# Sonde.net
KiCad netlist of a schematic drawn in EAGLE
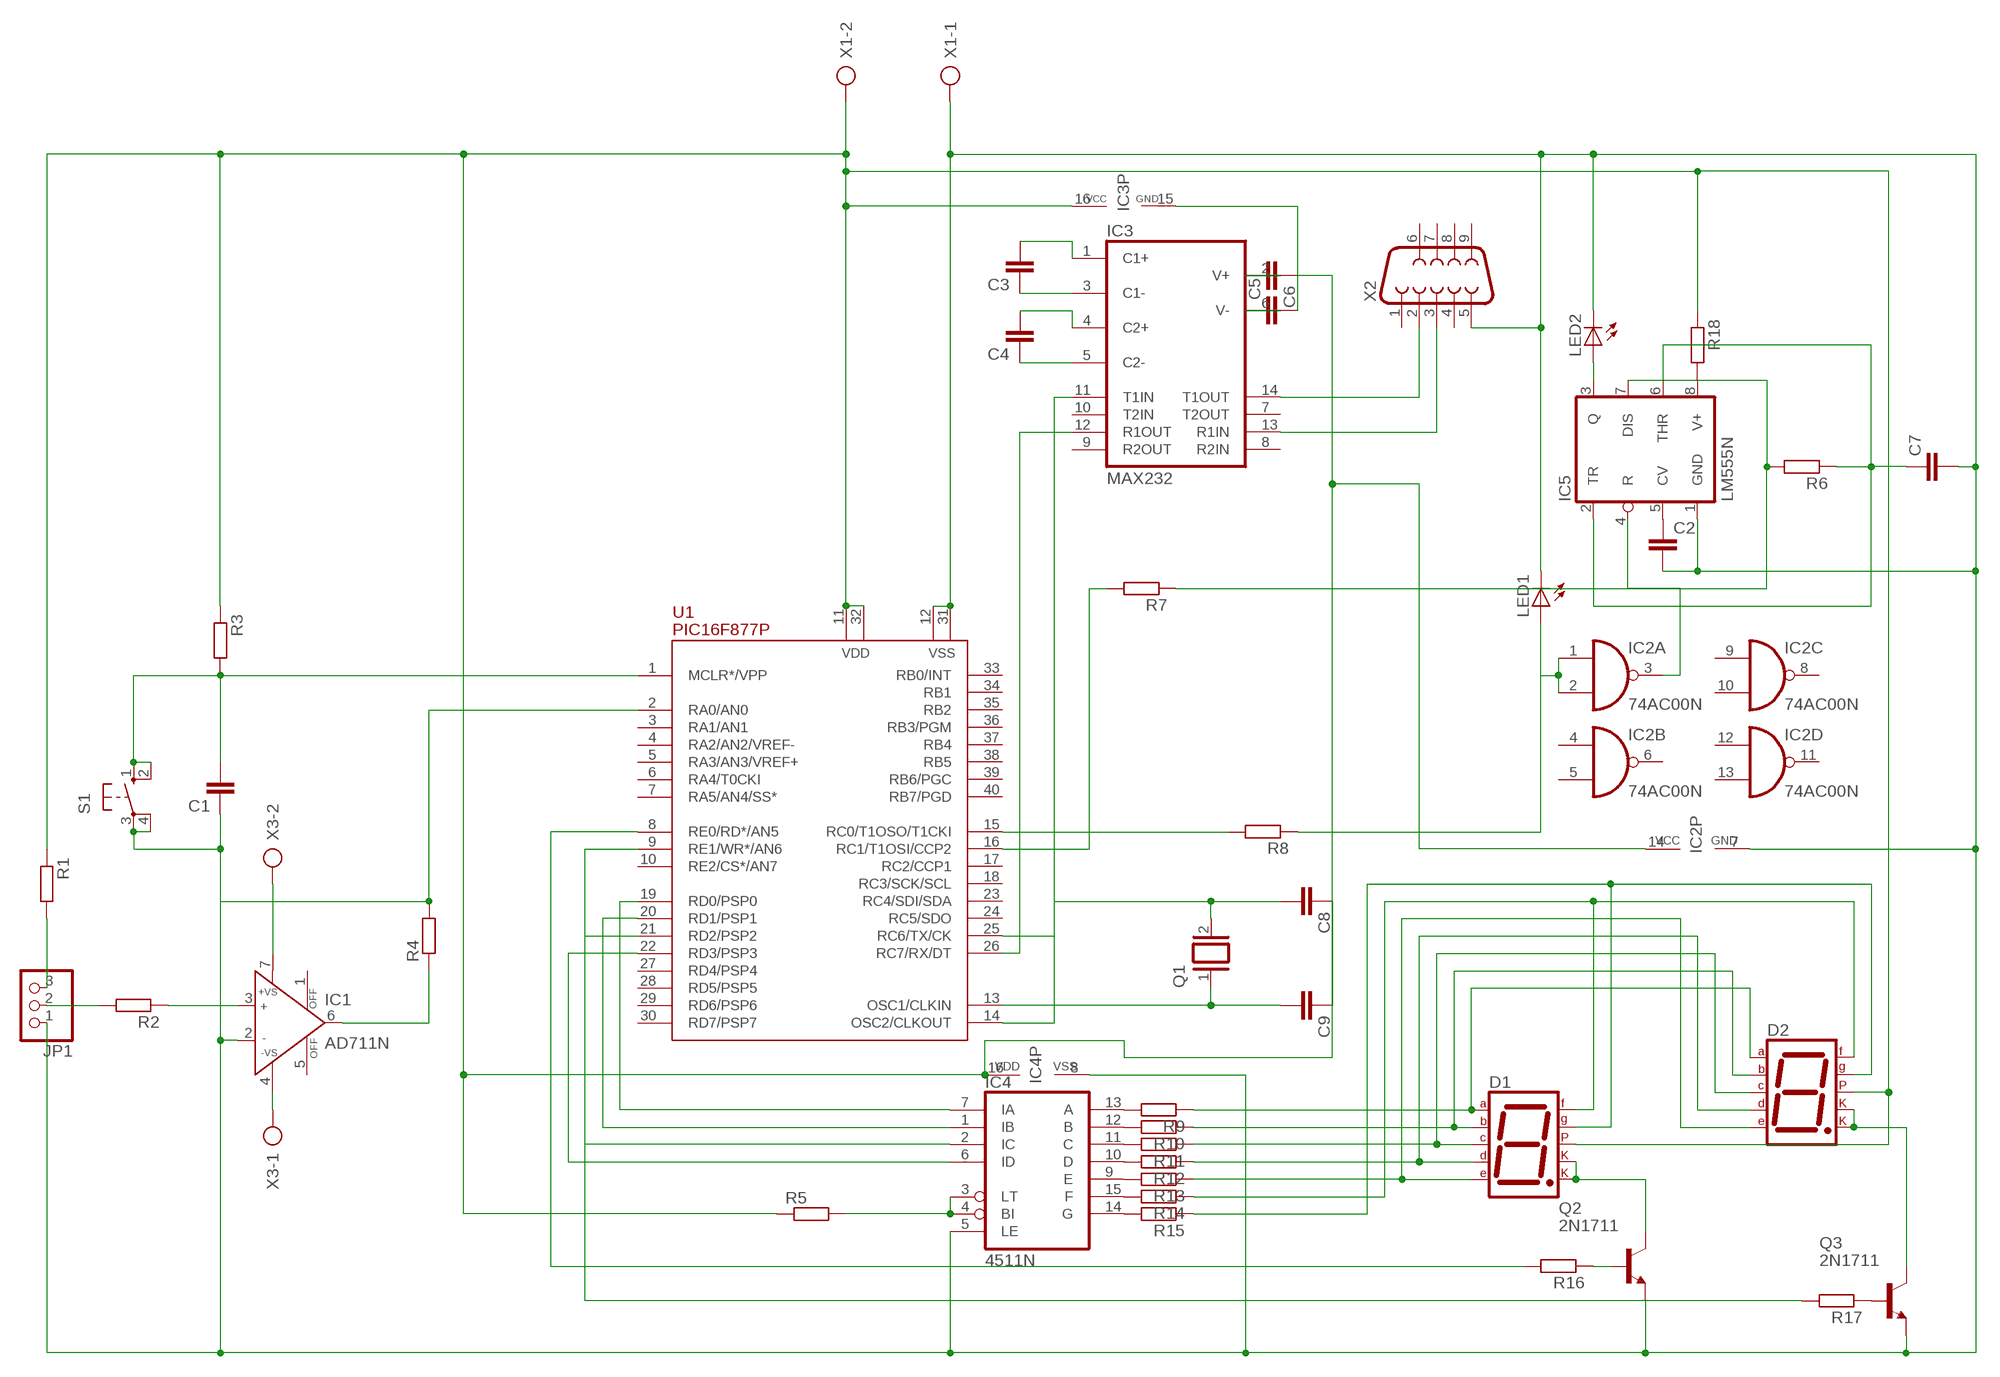
[diagram p0: schematic, sheet 1]

(export (version "E")
  (design (tool "Eeschema 10.0.6"))
  (components
    (comp (ref "C1")
      (value "C-EU025-024X044")
      (footprint "eagle-import:C025-024X044")
      (libsource (lib "eagle-import") (part "C-EU025-024X044"))
    )
    (comp (ref "C2")
      (value "C-EU025-024X044")
      (footprint "eagle-import:C025-024X044")
      (libsource (lib "eagle-import") (part "C-EU025-024X044"))
    )
    (comp (ref "C3")
      (value "C-EU025-024X044")
      (footprint "eagle-import:C025-024X044")
      (libsource (lib "eagle-import") (part "C-EU025-024X044"))
    )
    (comp (ref "C4")
      (value "C-EU025-024X044")
      (footprint "eagle-import:C025-024X044")
      (libsource (lib "eagle-import") (part "C-EU025-024X044"))
    )
    (comp (ref "C5")
      (value "C-EU025-024X044")
      (footprint "eagle-import:C025-024X044")
      (libsource (lib "eagle-import") (part "C-EU025-024X044"))
    )
    (comp (ref "C6")
      (value "C-EU025-024X044")
      (footprint "eagle-import:C025-024X044")
      (libsource (lib "eagle-import") (part "C-EU025-024X044"))
    )
    (comp (ref "C7")
      (value "C-EU025-024X044")
      (footprint "eagle-import:C025-024X044")
      (libsource (lib "eagle-import") (part "C-EU025-024X044"))
    )
    (comp (ref "C8")
      (value "C-EU025-024X044")
      (footprint "eagle-import:C025-024X044")
      (libsource (lib "eagle-import") (part "C-EU025-024X044"))
    )
    (comp (ref "C9")
      (value "C-EU025-024X044")
      (footprint "eagle-import:C025-024X044")
      (libsource (lib "eagle-import") (part "C-EU025-024X044"))
    )
    (comp (ref "D1")
      (value "7SEG-CK")
      (footprint "eagle-import:7SEG-13")
      (libsource (lib "eagle-import") (part "7SEG-CK"))
    )
    (comp (ref "D2")
      (value "7SEG-CK")
      (footprint "eagle-import:7SEG-13")
      (libsource (lib "eagle-import") (part "7SEG-CK"))
    )
    (comp (ref "IC1")
      (value "AD711N")
      (footprint "eagle-import:DIL08")
      (fields (field (name "MPN") "AD711BQ"))
      (libsource (lib "eagle-import") (part "AD711N"))
    )
    (comp (ref "IC2")
      (value "74AC00N")
      (footprint "eagle-import:DIL14")
      (libsource (lib "eagle-import") (part "7400NAC"))
    )
    (comp (ref "IC3")
      (value "MAX232")
      (footprint "eagle-import:DIL16")
      (fields (field (name "MF") "MAXIM") (field (name "MPN") "MAX232ACPE+"))
      (libsource (lib "eagle-import") (part "MAX232"))
    )
    (comp (ref "IC4")
      (value "4511N")
      (footprint "eagle-import:DIL16")
      (libsource (lib "eagle-import") (part "4511N"))
    )
    (comp (ref "IC5")
      (value "LM555N")
      (footprint "eagle-import:DIL08")
      (libsource (lib "eagle-import") (part "555NLM"))
    )
    (comp (ref "JP1")
      (value "PINHD-1X3")
      (footprint "eagle-import:1X03")
      (libsource (lib "eagle-import") (part "PINHD-1X3"))
    )
    (comp (ref "LED1")
      (value "LED_ELD260")
      (footprint "eagle-import:LED_LD260")
      (libsource (lib "eagle-import") (part "LED_ELD260"))
    )
    (comp (ref "LED2")
      (value "LED_ELD260")
      (footprint "eagle-import:LED_LD260")
      (libsource (lib "eagle-import") (part "LED_ELD260"))
    )
    (comp (ref "Q1")
      (value "XTAL/S")
      (footprint "eagle-import:QS")
      (libsource (lib "eagle-import") (part "XTAL/S"))
    )
    (comp (ref "Q2")
      (value "2N1711")
      (footprint "eagle-import:TO39")
      (libsource (lib "eagle-import") (part "2N1711"))
    )
    (comp (ref "Q3")
      (value "2N1711")
      (footprint "eagle-import:TO39")
      (libsource (lib "eagle-import") (part "2N1711"))
    )
    (comp (ref "R1")
      (value "R-EU_0207/10")
      (footprint "eagle-import:0207_10")
      (libsource (lib "eagle-import") (part "R-EU_0207/10"))
    )
    (comp (ref "R2")
      (value "R-EU_0207/10")
      (footprint "eagle-import:0207_10")
      (libsource (lib "eagle-import") (part "R-EU_0207/10"))
    )
    (comp (ref "R3")
      (value "R-EU_0207/10")
      (footprint "eagle-import:0207_10")
      (libsource (lib "eagle-import") (part "R-EU_0207/10"))
    )
    (comp (ref "R4")
      (value "R-EU_0207/10")
      (footprint "eagle-import:0207_10")
      (libsource (lib "eagle-import") (part "R-EU_0207/10"))
    )
    (comp (ref "R5")
      (value "R-EU_0207/10")
      (footprint "eagle-import:0207_10")
      (libsource (lib "eagle-import") (part "R-EU_0207/10"))
    )
    (comp (ref "R6")
      (value "R-EU_0207/10")
      (footprint "eagle-import:0207_10")
      (libsource (lib "eagle-import") (part "R-EU_0207/10"))
    )
    (comp (ref "R7")
      (value "R-EU_0207/10")
      (footprint "eagle-import:0207_10")
      (libsource (lib "eagle-import") (part "R-EU_0207/10"))
    )
    (comp (ref "R8")
      (value "R-EU_0207/10")
      (footprint "eagle-import:0207_10")
      (libsource (lib "eagle-import") (part "R-EU_0207/10"))
    )
    (comp (ref "R9")
      (value "R-EU_0207/10")
      (footprint "eagle-import:0207_10")
      (libsource (lib "eagle-import") (part "R-EU_0207/10"))
    )
    (comp (ref "R10")
      (value "R-EU_0207/10")
      (footprint "eagle-import:0207_10")
      (libsource (lib "eagle-import") (part "R-EU_0207/10"))
    )
    (comp (ref "R11")
      (value "R-EU_0207/10")
      (footprint "eagle-import:0207_10")
      (libsource (lib "eagle-import") (part "R-EU_0207/10"))
    )
    (comp (ref "R12")
      (value "R-EU_0207/10")
      (footprint "eagle-import:0207_10")
      (libsource (lib "eagle-import") (part "R-EU_0207/10"))
    )
    (comp (ref "R13")
      (value "R-EU_0207/10")
      (footprint "eagle-import:0207_10")
      (libsource (lib "eagle-import") (part "R-EU_0207/10"))
    )
    (comp (ref "R14")
      (value "R-EU_0207/10")
      (footprint "eagle-import:0207_10")
      (libsource (lib "eagle-import") (part "R-EU_0207/10"))
    )
    (comp (ref "R15")
      (value "R-EU_0207/10")
      (footprint "eagle-import:0207_10")
      (libsource (lib "eagle-import") (part "R-EU_0207/10"))
    )
    (comp (ref "R16")
      (value "R-EU_0207/10")
      (footprint "eagle-import:0207_10")
      (libsource (lib "eagle-import") (part "R-EU_0207/10"))
    )
    (comp (ref "R17")
      (value "R-EU_0207/10")
      (footprint "eagle-import:0207_10")
      (libsource (lib "eagle-import") (part "R-EU_0207/10"))
    )
    (comp (ref "R18")
      (value "R-EU_0207/10")
      (footprint "eagle-import:0207_10")
      (libsource (lib "eagle-import") (part "R-EU_0207/10"))
    )
    (comp (ref "S1")
      (value "10-XX")
      (footprint "eagle-import:B3F-10XX")
      (fields (field (name "MPN") "B3F-1000"))
      (libsource (lib "eagle-import") (part "10-XX"))
    )
    (comp (ref "U1")
      (value "PIC16F877P")
      (footprint "eagle-import:DIL40")
      (libsource (lib "eagle-import") (part "PIC16F877P"))
    )
    (comp (ref "X1")
      (value "AK300/2")
      (footprint "eagle-import:AK300_2")
      (libsource (lib "eagle-import") (part "AK300/2"))
    )
    (comp (ref "X2")
      (value "F09V")
      (footprint "eagle-import:F09V")
      (libsource (lib "eagle-import") (part "F09V"))
    )
    (comp (ref "X3")
      (value "AK300/2")
      (footprint "eagle-import:AK300_2")
      (libsource (lib "eagle-import") (part "AK300/2"))
    )
  )
  (nets
    (net (code "1") (name "Net-(C8-Pad1)") (class "Default")
      (node (ref "C8") (pin "1") (pinfunction "1_1") (pintype "passive"))
      (node (ref "C9") (pin "1") (pinfunction "1_1") (pintype "passive"))
    )
    (net (code "2") (name "Net-(D1-A)") (class "Default")
      (node (ref "D1") (pin "7") (pinfunction "A_7") (pintype "passive"))
      (node (ref "D2") (pin "7") (pinfunction "A_7") (pintype "passive"))
      (node (ref "R9") (pin "1") (pinfunction "1_1") (pintype "passive"))
    )
    (net (code "3") (name "Net-(D1-B)") (class "Default")
      (node (ref "D1") (pin "6") (pinfunction "B_6") (pintype "passive"))
      (node (ref "D2") (pin "6") (pinfunction "B_6") (pintype "passive"))
      (node (ref "R10") (pin "1") (pinfunction "1_1") (pintype "passive"))
    )
    (net (code "4") (name "Net-(D1-C)") (class "Default")
      (node (ref "D1") (pin "4") (pinfunction "C_4") (pintype "passive"))
      (node (ref "D2") (pin "4") (pinfunction "C_4") (pintype "passive"))
      (node (ref "R11") (pin "1") (pinfunction "1_1") (pintype "passive"))
    )
    (net (code "5") (name "Net-(D1-CK1)") (class "Default")
      (node (ref "D1") (pin "3") (pinfunction "CK1_3") (pintype "passive"))
      (node (ref "D1") (pin "8") (pinfunction "CK2_8") (pintype "passive"))
      (node (ref "Q2") (pin "3") (pinfunction "C_3") (pintype "passive"))
    )
    (net (code "6") (name "Net-(D1-D)") (class "Default")
      (node (ref "D1") (pin "2") (pinfunction "D_2") (pintype "passive"))
      (node (ref "D2") (pin "2") (pinfunction "D_2") (pintype "passive"))
      (node (ref "R12") (pin "1") (pinfunction "1_1") (pintype "passive"))
    )
    (net (code "7") (name "Net-(D1-DP)") (class "Default")
      (node (ref "C6") (pin "1") (pinfunction "1_1") (pintype "passive"))
      (node (ref "D1") (pin "5") (pinfunction "DP_5") (pintype "passive"))
      (node (ref "D2") (pin "5") (pinfunction "DP_5") (pintype "passive"))
      (node (ref "IC2") (pin "14") (pinfunction "VCC_14") (pintype "power_in"))
      (node (ref "IC3") (pin "16") (pinfunction "VCC_16") (pintype "power_in"))
      (node (ref "IC4") (pin "16") (pinfunction "VDD_16") (pintype "power_in"))
      (node (ref "R1") (pin "1") (pinfunction "1_1") (pintype "passive"))
      (node (ref "R18") (pin "1") (pinfunction "1_1") (pintype "passive"))
      (node (ref "R3") (pin "1") (pinfunction "1_1") (pintype "passive"))
      (node (ref "R5") (pin "1") (pinfunction "1_1") (pintype "passive"))
      (node (ref "U1") (pin "11") (pinfunction "VDD_11") (pintype "bidirectional"))
      (node (ref "U1") (pin "32") (pinfunction "VDD_32") (pintype "bidirectional"))
      (node (ref "X1") (pin "2") (pinfunction "KL_2") (pintype "passive"))
    )
    (net (code "8") (name "Net-(D1-E)") (class "Default")
      (node (ref "D1") (pin "1") (pinfunction "E_1") (pintype "passive"))
      (node (ref "D2") (pin "1") (pinfunction "E_1") (pintype "passive"))
      (node (ref "R13") (pin "1") (pinfunction "1_1") (pintype "passive"))
    )
    (net (code "9") (name "Net-(D1-F)") (class "Default")
      (node (ref "D1") (pin "9") (pinfunction "F_9") (pintype "passive"))
      (node (ref "D2") (pin "9") (pinfunction "F_9") (pintype "passive"))
      (node (ref "R14") (pin "1") (pinfunction "1_1") (pintype "passive"))
    )
    (net (code "10") (name "Net-(D1-G)") (class "Default")
      (node (ref "D1") (pin "10") (pinfunction "G_10") (pintype "passive"))
      (node (ref "D2") (pin "10") (pinfunction "G_10") (pintype "passive"))
      (node (ref "R15") (pin "1") (pinfunction "1_1") (pintype "passive"))
    )
    (net (code "11") (name "Net-(D2-CK1)") (class "Default")
      (node (ref "D2") (pin "3") (pinfunction "CK1_3") (pintype "passive"))
      (node (ref "D2") (pin "8") (pinfunction "CK2_8") (pintype "passive"))
      (node (ref "Q3") (pin "3") (pinfunction "C_3") (pintype "passive"))
    )
    (net (code "12") (name "Net-(IC1-+VS)") (class "Default")
      (node (ref "IC1") (pin "7") (pinfunction "+VS_7") (pintype "input"))
      (node (ref "X3") (pin "2") (pinfunction "KL_2") (pintype "passive"))
    )
    (net (code "13") (name "Net-(IC1--VS)") (class "Default")
      (node (ref "IC1") (pin "4") (pinfunction "-VS_4") (pintype "input"))
      (node (ref "X3") (pin "1") (pinfunction "KL_1") (pintype "passive"))
    )
    (net (code "14") (name "Net-(IC1-IN+)") (class "Default")
      (node (ref "IC1") (pin "3") (pinfunction "IN+_3") (pintype "input"))
      (node (ref "R2") (pin "1") (pinfunction "1_1") (pintype "passive"))
    )
    (net (code "15") (name "Net-(IC1-IN-)") (class "Default")
      (node (ref "C1") (pin "1") (pinfunction "1_1") (pintype "passive"))
      (node (ref "C2") (pin "2") (pinfunction "2_2") (pintype "passive"))
      (node (ref "C7") (pin "2") (pinfunction "2_2") (pintype "passive"))
      (node (ref "IC1") (pin "2") (pinfunction "IN-_2") (pintype "input"))
      (node (ref "IC2") (pin "7") (pinfunction "GND_7") (pintype "power_in"))
      (node (ref "IC4") (pin "5") (pinfunction "LE_5") (pintype "input"))
      (node (ref "IC4") (pin "8") (pinfunction "VSS_8") (pintype "power_in"))
      (node (ref "IC5") (pin "1") (pinfunction "GND_1") (pintype "power_in"))
      (node (ref "JP1") (pin "1") (pinfunction "1_1") (pintype "passive"))
      (node (ref "LED1") (pin "K") (pinfunction "C_K") (pintype "passive"))
      (node (ref "LED2") (pin "K") (pinfunction "C_K") (pintype "passive"))
      (node (ref "Q2") (pin "1") (pinfunction "E_1") (pintype "passive"))
      (node (ref "Q3") (pin "1") (pinfunction "E_1") (pintype "passive"))
      (node (ref "R4") (pin "2") (pinfunction "2_2") (pintype "passive"))
      (node (ref "S1") (pin "3") (pinfunction "P_3") (pintype "passive"))
      (node (ref "S1") (pin "4") (pinfunction "P1_4") (pintype "passive"))
      (node (ref "U1") (pin "12") (pinfunction "VSS_12") (pintype "bidirectional"))
      (node (ref "U1") (pin "2") (pinfunction "RA0/AN0_2") (pintype "bidirectional"))
      (node (ref "U1") (pin "31") (pinfunction "VSS_31") (pintype "bidirectional"))
      (node (ref "X1") (pin "1") (pinfunction "KL_1") (pintype "passive"))
      (node (ref "X2") (pin "5") (pinfunction "5_5") (pintype "passive"))
    )
    (net (code "16") (name "Net-(IC1-OUT)") (class "Default")
      (node (ref "IC1") (pin "6") (pinfunction "OUT_6") (pintype "output"))
      (node (ref "R4") (pin "1") (pinfunction "1_1") (pintype "passive"))
    )
    (net (code "17") (name "Net-(IC2A-I0)") (class "Default")
      (node (ref "IC2") (pin "1") (pinfunction "I0_1") (pintype "input"))
      (node (ref "IC2") (pin "2") (pinfunction "I1_2") (pintype "input"))
      (node (ref "LED1") (pin "A") (pinfunction "A_A") (pintype "passive"))
      (node (ref "R8") (pin "1") (pinfunction "1_1") (pintype "passive"))
    )
    (net (code "18") (name "Net-(IC2A-O)") (class "Default")
      (node (ref "IC2") (pin "3") (pinfunction "O_3") (pintype "output"))
      (node (ref "IC5") (pin "4") (pinfunction "R_4") (pintype "input"))
    )
    (net (code "19") (name "Net-(IC3A-C1+)") (class "Default")
      (node (ref "C3") (pin "2") (pinfunction "2_2") (pintype "passive"))
      (node (ref "IC3") (pin "1") (pinfunction "C1+_1") (pintype "bidirectional"))
    )
    (net (code "20") (name "Net-(IC3A-C1-)") (class "Default")
      (node (ref "C3") (pin "1") (pinfunction "1_1") (pintype "passive"))
      (node (ref "IC3") (pin "3") (pinfunction "C1-_3") (pintype "bidirectional"))
    )
    (net (code "21") (name "Net-(IC3A-C2+)") (class "Default")
      (node (ref "C4") (pin "2") (pinfunction "2_2") (pintype "passive"))
      (node (ref "IC3") (pin "4") (pinfunction "C2+_4") (pintype "bidirectional"))
    )
    (net (code "22") (name "Net-(IC3A-C2-)") (class "Default")
      (node (ref "C4") (pin "1") (pinfunction "1_1") (pintype "passive"))
      (node (ref "IC3") (pin "5") (pinfunction "C2-_5") (pintype "bidirectional"))
    )
    (net (code "23") (name "Net-(IC3A-R1IN)") (class "Default")
      (node (ref "IC3") (pin "13") (pinfunction "R1IN_13") (pintype "input"))
      (node (ref "X2") (pin "3") (pinfunction "3_3") (pintype "passive"))
    )
    (net (code "24") (name "Net-(IC3A-R1OUT)") (class "Default")
      (node (ref "IC3") (pin "12") (pinfunction "R1OUT_12") (pintype "output"))
      (node (ref "U1") (pin "26") (pinfunction "RC7/RX/DT_26") (pintype "bidirectional"))
    )
    (net (code "25") (name "Net-(IC3A-T1IN)") (class "Default")
      (node (ref "IC3") (pin "11") (pinfunction "T1IN_11") (pintype "input"))
      (node (ref "U1") (pin "25") (pinfunction "RC6/TX/CK_25") (pintype "bidirectional"))
    )
    (net (code "26") (name "Net-(IC3A-T1OUT)") (class "Default")
      (node (ref "IC3") (pin "14") (pinfunction "T1OUT_14") (pintype "output"))
      (node (ref "X2") (pin "2") (pinfunction "2_2") (pintype "passive"))
    )
    (net (code "27") (name "Net-(IC3A-V+)") (class "Default")
      (node (ref "C6") (pin "2") (pinfunction "2_2") (pintype "passive"))
      (node (ref "IC3") (pin "2") (pinfunction "V+_2") (pintype "bidirectional"))
    )
    (net (code "28") (name "Net-(IC3A-V-)") (class "Default")
      (node (ref "C5") (pin "1") (pinfunction "1_1") (pintype "passive"))
      (node (ref "IC3") (pin "6") (pinfunction "V-_6") (pintype "bidirectional"))
    )
    (net (code "29") (name "Net-(IC3B-GND)") (class "Default")
      (node (ref "C5") (pin "2") (pinfunction "2_2") (pintype "passive"))
      (node (ref "IC3") (pin "15") (pinfunction "GND_15") (pintype "power_in"))
    )
    (net (code "30") (name "Net-(IC4A-A)") (class "Default")
      (node (ref "IC4") (pin "13") (pinfunction "A_13") (pintype "output"))
      (node (ref "R9") (pin "2") (pinfunction "2_2") (pintype "passive"))
    )
    (net (code "31") (name "Net-(IC4A-B)") (class "Default")
      (node (ref "IC4") (pin "12") (pinfunction "B_12") (pintype "output"))
      (node (ref "R10") (pin "2") (pinfunction "2_2") (pintype "passive"))
    )
    (net (code "32") (name "Net-(IC4A-BI)") (class "Default")
      (node (ref "IC4") (pin "3") (pinfunction "LT_3") (pintype "input"))
      (node (ref "IC4") (pin "4") (pinfunction "BI_4") (pintype "input"))
      (node (ref "R5") (pin "2") (pinfunction "2_2") (pintype "passive"))
    )
    (net (code "33") (name "Net-(IC4A-C)") (class "Default")
      (node (ref "IC4") (pin "11") (pinfunction "C_11") (pintype "output"))
      (node (ref "R11") (pin "2") (pinfunction "2_2") (pintype "passive"))
    )
    (net (code "34") (name "Net-(IC4A-D)") (class "Default")
      (node (ref "IC4") (pin "10") (pinfunction "D_10") (pintype "output"))
      (node (ref "R12") (pin "2") (pinfunction "2_2") (pintype "passive"))
    )
    (net (code "35") (name "Net-(IC4A-E)") (class "Default")
      (node (ref "IC4") (pin "9") (pinfunction "E_9") (pintype "output"))
      (node (ref "R13") (pin "2") (pinfunction "2_2") (pintype "passive"))
    )
    (net (code "36") (name "Net-(IC4A-F)") (class "Default")
      (node (ref "IC4") (pin "15") (pinfunction "F_15") (pintype "output"))
      (node (ref "R14") (pin "2") (pinfunction "2_2") (pintype "passive"))
    )
    (net (code "37") (name "Net-(IC4A-G)") (class "Default")
      (node (ref "IC4") (pin "14") (pinfunction "G_14") (pintype "output"))
      (node (ref "R15") (pin "2") (pinfunction "2_2") (pintype "passive"))
    )
    (net (code "38") (name "Net-(IC4A-IA)") (class "Default")
      (node (ref "IC4") (pin "7") (pinfunction "IA_7") (pintype "input"))
      (node (ref "U1") (pin "19") (pinfunction "RD0/PSP0_19") (pintype "bidirectional"))
    )
    (net (code "39") (name "Net-(IC4A-IB)") (class "Default")
      (node (ref "IC4") (pin "1") (pinfunction "IB_1") (pintype "input"))
      (node (ref "U1") (pin "20") (pinfunction "RD1/PSP1_20") (pintype "bidirectional"))
    )
    (net (code "40") (name "Net-(IC4A-IC)") (class "Default")
      (node (ref "IC4") (pin "2") (pinfunction "IC_2") (pintype "input"))
      (node (ref "U1") (pin "21") (pinfunction "RD2/PSP2_21") (pintype "bidirectional"))
    )
    (net (code "41") (name "Net-(IC4A-ID)") (class "Default")
      (node (ref "IC4") (pin "6") (pinfunction "ID_6") (pintype "input"))
      (node (ref "U1") (pin "22") (pinfunction "RD3/PSP3_22") (pintype "bidirectional"))
    )
    (net (code "42") (name "Net-(IC5-CV)") (class "Default")
      (node (ref "C2") (pin "1") (pinfunction "1_1") (pintype "passive"))
      (node (ref "IC5") (pin "5") (pinfunction "CV_5") (pintype "input"))
    )
    (net (code "43") (name "Net-(IC5-DIS)") (class "Default")
      (node (ref "IC5") (pin "7") (pinfunction "DIS_7") (pintype "input"))
      (node (ref "R6") (pin "2") (pinfunction "2_2") (pintype "passive"))
      (node (ref "R7") (pin "1") (pinfunction "1_1") (pintype "passive"))
    )
    (net (code "44") (name "Net-(IC5-Q)") (class "Default")
      (node (ref "IC5") (pin "3") (pinfunction "Q_3") (pintype "output"))
      (node (ref "LED2") (pin "A") (pinfunction "A_A") (pintype "passive"))
    )
    (net (code "45") (name "Net-(IC5-THR)") (class "Default")
      (node (ref "C7") (pin "1") (pinfunction "1_1") (pintype "passive"))
      (node (ref "IC5") (pin "2") (pinfunction "TR_2") (pintype "input"))
      (node (ref "IC5") (pin "6") (pinfunction "THR_6") (pintype "input"))
      (node (ref "R6") (pin "1") (pinfunction "1_1") (pintype "passive"))
    )
    (net (code "46") (name "Net-(IC5-V+)") (class "Default")
      (node (ref "IC5") (pin "8") (pinfunction "V+_8") (pintype "power_in"))
      (node (ref "R18") (pin "2") (pinfunction "2_2") (pintype "passive"))
    )
    (net (code "47") (name "Net-(JP1-Pad2)") (class "Default")
      (node (ref "JP1") (pin "2") (pinfunction "2_2") (pintype "passive"))
      (node (ref "R2") (pin "2") (pinfunction "2_2") (pintype "passive"))
    )
    (net (code "48") (name "Net-(JP1-Pad3)") (class "Default")
      (node (ref "JP1") (pin "3") (pinfunction "3_3") (pintype "passive"))
      (node (ref "R1") (pin "2") (pinfunction "2_2") (pintype "passive"))
    )
    (net (code "49") (name "Net-(Q2-B)") (class "Default")
      (node (ref "Q2") (pin "2") (pinfunction "B_2") (pintype "passive"))
      (node (ref "R16") (pin "1") (pinfunction "1_1") (pintype "passive"))
    )
    (net (code "50") (name "Net-(Q3-B)") (class "Default")
      (node (ref "Q3") (pin "2") (pinfunction "B_2") (pintype "passive"))
      (node (ref "R17") (pin "1") (pinfunction "1_1") (pintype "passive"))
    )
    (net (code "51") (name "Net-(S1-S)") (class "Default")
      (node (ref "C1") (pin "2") (pinfunction "2_2") (pintype "passive"))
      (node (ref "R3") (pin "2") (pinfunction "2_2") (pintype "passive"))
      (node (ref "S1") (pin "1") (pinfunction "S_1") (pintype "passive"))
      (node (ref "S1") (pin "2") (pinfunction "S1_2") (pintype "passive"))
      (node (ref "U1") (pin "1") (pinfunction "MCLR*/VPP_1") (pintype "input"))
    )
    (net (code "52") (name "Net-(U1-OSC1{slash}CLKIN)") (class "Default")
      (node (ref "C9") (pin "2") (pinfunction "2_2") (pintype "passive"))
      (node (ref "Q1") (pin "1") (pinfunction "1_1") (pintype "passive"))
      (node (ref "U1") (pin "13") (pinfunction "OSC1/CLKIN_13") (pintype "input"))
    )
    (net (code "53") (name "Net-(U1-OSC2{slash}CLKOUT)") (class "Default")
      (node (ref "C8") (pin "2") (pinfunction "2_2") (pintype "passive"))
      (node (ref "Q1") (pin "2") (pinfunction "2_2") (pintype "passive"))
      (node (ref "U1") (pin "14") (pinfunction "OSC2/CLKOUT_14") (pintype "output"))
    )
    (net (code "54") (name "Net-(U1-RC0{slash}T1OSO{slash}T1CKI)") (class "Default")
      (node (ref "R8") (pin "2") (pinfunction "2_2") (pintype "passive"))
      (node (ref "U1") (pin "15") (pinfunction "RC0/T1OSO/T1CKI_15") (pintype "bidirectional"))
    )
    (net (code "55") (name "Net-(U1-RC1{slash}T1OSI{slash}CCP2)") (class "Default")
      (node (ref "R7") (pin "2") (pinfunction "2_2") (pintype "passive"))
      (node (ref "U1") (pin "16") (pinfunction "RC1/T1OSI/CCP2_16") (pintype "bidirectional"))
    )
    (net (code "56") (name "Net-(U1-RE0{slash}RD*{slash}AN5)") (class "Default")
      (node (ref "R16") (pin "2") (pinfunction "2_2") (pintype "passive"))
      (node (ref "U1") (pin "8") (pinfunction "RE0/RD*/AN5_8") (pintype "bidirectional"))
    )
    (net (code "57") (name "Net-(U1-RE1{slash}WR*{slash}AN6)") (class "Default")
      (node (ref "R17") (pin "2") (pinfunction "2_2") (pintype "passive"))
      (node (ref "U1") (pin "9") (pinfunction "RE1/WR*/AN6_9") (pintype "bidirectional"))
    )
    (net (code "58") (name "unconnected-(IC1-OFF-Pad1)") (class "Default")
      (node (ref "IC1") (pin "1") (pinfunction "OFF_1") (pintype "passive"))
    )
    (net (code "59") (name "unconnected-(IC1-OFF-Pad5)") (class "Default")
      (node (ref "IC1") (pin "5") (pinfunction "OFF_5") (pintype "passive"))
    )
    (net (code "60") (name "unconnected-(IC2B-I0-Pad4)") (class "Default")
      (node (ref "IC2") (pin "4") (pinfunction "I0_4") (pintype "input"))
    )
    (net (code "61") (name "unconnected-(IC2B-I1-Pad5)") (class "Default")
      (node (ref "IC2") (pin "5") (pinfunction "I1_5") (pintype "input"))
    )
    (net (code "62") (name "unconnected-(IC2B-O-Pad6)") (class "Default")
      (node (ref "IC2") (pin "6") (pinfunction "O_6") (pintype "output"))
    )
    (net (code "63") (name "unconnected-(IC2C-I0-Pad9)") (class "Default")
      (node (ref "IC2") (pin "9") (pinfunction "I0_9") (pintype "input"))
    )
    (net (code "64") (name "unconnected-(IC2C-I1-Pad10)") (class "Default")
      (node (ref "IC2") (pin "10") (pinfunction "I1_10") (pintype "input"))
    )
    (net (code "65") (name "unconnected-(IC2C-O-Pad8)") (class "Default")
      (node (ref "IC2") (pin "8") (pinfunction "O_8") (pintype "output"))
    )
    (net (code "66") (name "unconnected-(IC2D-I0-Pad12)") (class "Default")
      (node (ref "IC2") (pin "12") (pinfunction "I0_12") (pintype "input"))
    )
    (net (code "67") (name "unconnected-(IC2D-I1-Pad13)") (class "Default")
      (node (ref "IC2") (pin "13") (pinfunction "I1_13") (pintype "input"))
    )
    (net (code "68") (name "unconnected-(IC2D-O-Pad11)") (class "Default")
      (node (ref "IC2") (pin "11") (pinfunction "O_11") (pintype "output"))
    )
    (net (code "69") (name "unconnected-(IC3A-R2IN-Pad8)") (class "Default")
      (node (ref "IC3") (pin "8") (pinfunction "R2IN_8") (pintype "input"))
    )
    (net (code "70") (name "unconnected-(IC3A-R2OUT-Pad9)") (class "Default")
      (node (ref "IC3") (pin "9") (pinfunction "R2OUT_9") (pintype "output"))
    )
    (net (code "71") (name "unconnected-(IC3A-T2IN-Pad10)") (class "Default")
      (node (ref "IC3") (pin "10") (pinfunction "T2IN_10") (pintype "input"))
    )
    (net (code "72") (name "unconnected-(IC3A-T2OUT-Pad7)") (class "Default")
      (node (ref "IC3") (pin "7") (pinfunction "T2OUT_7") (pintype "output"))
    )
    (net (code "73") (name "unconnected-(U1-RA1{slash}AN1-Pad3)") (class "Default")
      (node (ref "U1") (pin "3") (pinfunction "RA1/AN1_3") (pintype "bidirectional"))
    )
    (net (code "74") (name "unconnected-(U1-RA2{slash}AN2{slash}VREF--Pad4)") (class "Default")
      (node (ref "U1") (pin "4") (pinfunction "RA2/AN2/VREF-_4") (pintype "bidirectional"))
    )
    (net (code "75") (name "unconnected-(U1-RA3{slash}AN3{slash}VREF+-Pad5)") (class "Default")
      (node (ref "U1") (pin "5") (pinfunction "RA3/AN3/VREF+_5") (pintype "bidirectional"))
    )
    (net (code "76") (name "unconnected-(U1-RA4{slash}T0CKI-Pad6)") (class "Default")
      (node (ref "U1") (pin "6") (pinfunction "RA4/T0CKI_6") (pintype "bidirectional"))
    )
    (net (code "77") (name "unconnected-(U1-RA5{slash}AN4{slash}SS*-Pad7)") (class "Default")
      (node (ref "U1") (pin "7") (pinfunction "RA5/AN4/SS*_7") (pintype "bidirectional"))
    )
    (net (code "78") (name "unconnected-(U1-RB0{slash}INT-Pad33)") (class "Default")
      (node (ref "U1") (pin "33") (pinfunction "RB0/INT_33") (pintype "bidirectional"))
    )
    (net (code "79") (name "unconnected-(U1-RB1-Pad34)") (class "Default")
      (node (ref "U1") (pin "34") (pinfunction "RB1_34") (pintype "bidirectional"))
    )
    (net (code "80") (name "unconnected-(U1-RB2-Pad35)") (class "Default")
      (node (ref "U1") (pin "35") (pinfunction "RB2_35") (pintype "bidirectional"))
    )
    (net (code "81") (name "unconnected-(U1-RB3{slash}PGM-Pad36)") (class "Default")
      (node (ref "U1") (pin "36") (pinfunction "RB3/PGM_36") (pintype "bidirectional"))
    )
    (net (code "82") (name "unconnected-(U1-RB4-Pad37)") (class "Default")
      (node (ref "U1") (pin "37") (pinfunction "RB4_37") (pintype "bidirectional"))
    )
    (net (code "83") (name "unconnected-(U1-RB5-Pad38)") (class "Default")
      (node (ref "U1") (pin "38") (pinfunction "RB5_38") (pintype "bidirectional"))
    )
    (net (code "84") (name "unconnected-(U1-RB6{slash}PGC-Pad39)") (class "Default")
      (node (ref "U1") (pin "39") (pinfunction "RB6/PGC_39") (pintype "bidirectional"))
    )
    (net (code "85") (name "unconnected-(U1-RB7{slash}PGD-Pad40)") (class "Default")
      (node (ref "U1") (pin "40") (pinfunction "RB7/PGD_40") (pintype "bidirectional"))
    )
    (net (code "86") (name "unconnected-(U1-RC2{slash}CCP1-Pad17)") (class "Default")
      (node (ref "U1") (pin "17") (pinfunction "RC2/CCP1_17") (pintype "bidirectional"))
    )
    (net (code "87") (name "unconnected-(U1-RC3{slash}SCK{slash}SCL-Pad18)") (class "Default")
      (node (ref "U1") (pin "18") (pinfunction "RC3/SCK/SCL_18") (pintype "bidirectional"))
    )
    (net (code "88") (name "unconnected-(U1-RC4{slash}SDI{slash}SDA-Pad23)") (class "Default")
      (node (ref "U1") (pin "23") (pinfunction "RC4/SDI/SDA_23") (pintype "bidirectional"))
    )
    (net (code "89") (name "unconnected-(U1-RC5{slash}SDO-Pad24)") (class "Default")
      (node (ref "U1") (pin "24") (pinfunction "RC5/SDO_24") (pintype "bidirectional"))
    )
    (net (code "90") (name "unconnected-(U1-RD4{slash}PSP4-Pad27)") (class "Default")
      (node (ref "U1") (pin "27") (pinfunction "RD4/PSP4_27") (pintype "bidirectional"))
    )
    (net (code "91") (name "unconnected-(U1-RD5{slash}PSP5-Pad28)") (class "Default")
      (node (ref "U1") (pin "28") (pinfunction "RD5/PSP5_28") (pintype "bidirectional"))
    )
    (net (code "92") (name "unconnected-(U1-RD6{slash}PSP6-Pad29)") (class "Default")
      (node (ref "U1") (pin "29") (pinfunction "RD6/PSP6_29") (pintype "bidirectional"))
    )
    (net (code "93") (name "unconnected-(U1-RD7{slash}PSP7-Pad30)") (class "Default")
      (node (ref "U1") (pin "30") (pinfunction "RD7/PSP7_30") (pintype "bidirectional"))
    )
    (net (code "94") (name "unconnected-(U1-RE2{slash}CS*{slash}AN7-Pad10)") (class "Default")
      (node (ref "U1") (pin "10") (pinfunction "RE2/CS*/AN7_10") (pintype "bidirectional"))
    )
    (net (code "95") (name "unconnected-(X2-Pad1)") (class "Default")
      (node (ref "X2") (pin "1") (pinfunction "1_1") (pintype "passive"))
    )
    (net (code "96") (name "unconnected-(X2-Pad4)") (class "Default")
      (node (ref "X2") (pin "4") (pinfunction "4_4") (pintype "passive"))
    )
    (net (code "97") (name "unconnected-(X2-Pad6)") (class "Default")
      (node (ref "X2") (pin "6") (pinfunction "6_6") (pintype "passive"))
    )
    (net (code "98") (name "unconnected-(X2-Pad7)") (class "Default")
      (node (ref "X2") (pin "7") (pinfunction "7_7") (pintype "passive"))
    )
    (net (code "99") (name "unconnected-(X2-Pad8)") (class "Default")
      (node (ref "X2") (pin "8") (pinfunction "8_8") (pintype "passive"))
    )
    (net (code "100") (name "unconnected-(X2-Pad9)") (class "Default")
      (node (ref "X2") (pin "9") (pinfunction "9_9") (pintype "passive"))
    )
  )
)
